# Mono_Audio_Amp_TPA2005D1_v10.net
KiCad netlist of a schematic drawn in EAGLE
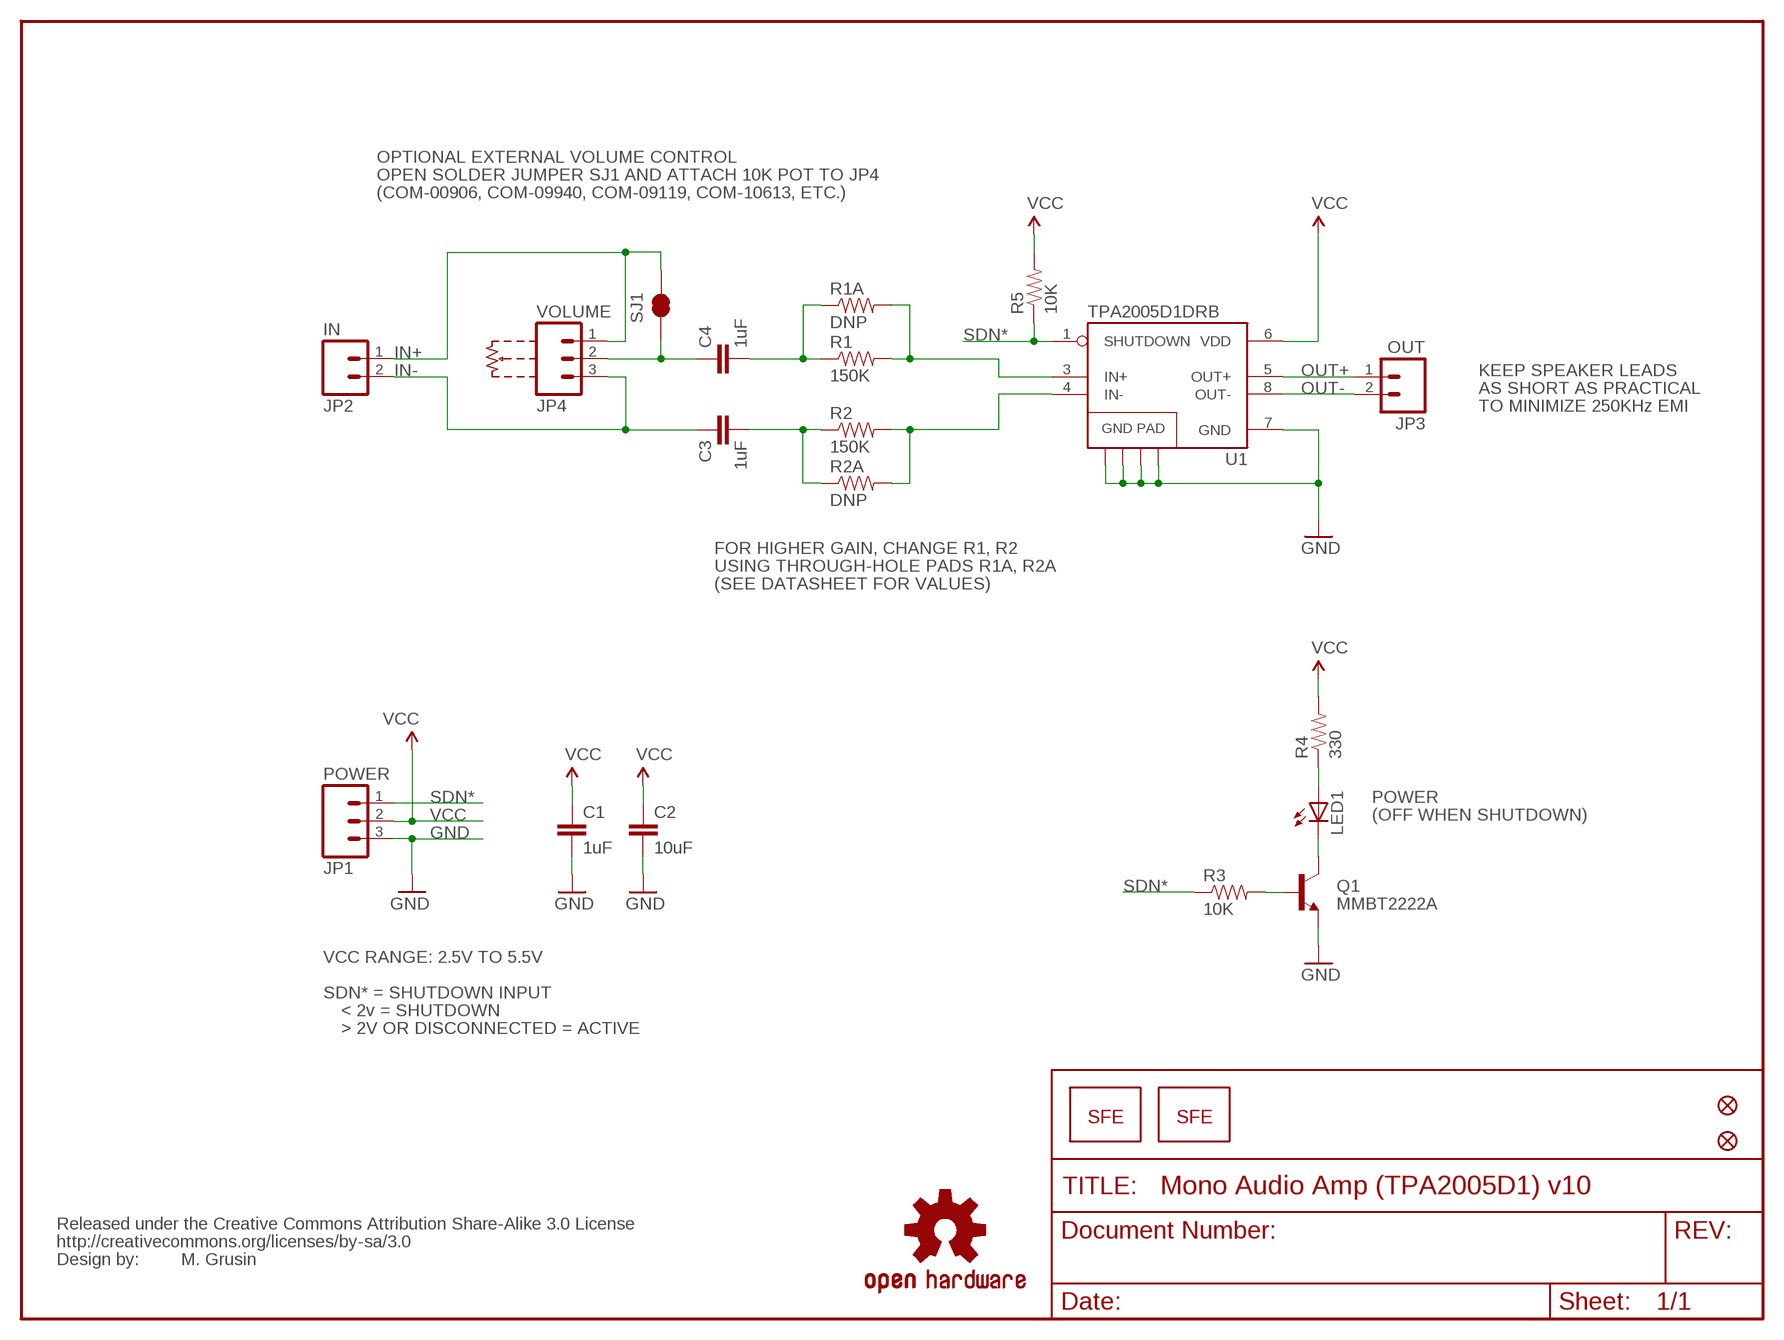
[diagram p0: schematic, sheet 1]

(export (version "E")
  (design (tool "Eeschema 10.0.6"))
  (components
    (comp (ref "C1")
      (value "1uF")
      (footprint "eagle-import:1206")
      (libsource (lib "eagle-import") (part "CAP1206"))
    )
    (comp (ref "C2")
      (value "10uF")
      (footprint "eagle-import:1206")
      (libsource (lib "eagle-import") (part "CAP1206"))
    )
    (comp (ref "C3")
      (value "1uF")
      (footprint "eagle-import:1206")
      (libsource (lib "eagle-import") (part "CAP1206"))
    )
    (comp (ref "C4")
      (value "1uF")
      (footprint "eagle-import:1206")
      (libsource (lib "eagle-import") (part "CAP1206"))
    )
    (comp (ref "JP1")
      (value "POWER")
      (footprint "eagle-import:1X03")
      (libsource (lib "eagle-import") (part "M03PTH"))
    )
    (comp (ref "JP2")
      (value "IN")
      (footprint "eagle-import:1X02")
      (libsource (lib "eagle-import") (part "M02PTH"))
    )
    (comp (ref "JP3")
      (value "OUT")
      (footprint "eagle-import:1X02")
      (libsource (lib "eagle-import") (part "M02PTH"))
    )
    (comp (ref "JP4")
      (value "VOLUME")
      (footprint "eagle-import:1X03")
      (libsource (lib "eagle-import") (part "M03PTH"))
    )
    (comp (ref "JP5")
      (value "FIDUCIALUFIDUCIAL")
      (footprint "eagle-import:MICRO-FIDUCIAL")
      (libsource (lib "eagle-import") (part "FIDUCIALUFIDUCIAL"))
    )
    (comp (ref "JP6")
      (value "FIDUCIALUFIDUCIAL")
      (footprint "eagle-import:MICRO-FIDUCIAL")
      (libsource (lib "eagle-import") (part "FIDUCIALUFIDUCIAL"))
    )
    (comp (ref "LED1")
      (value "LED0603")
      (footprint "eagle-import:LED-0603")
      (libsource (lib "eagle-import") (part "LED0603"))
    )
    (comp (ref "LOGO1")
      (value "LOGO-SFENW2")
      (footprint "eagle-import:SFE-NEW-WEB")
      (libsource (lib "eagle-import") (part "LOGO-SFENW2"))
    )
    (comp (ref "LOGO2")
      (value "LOGO-SFESK")
      (footprint "eagle-import:SFE-LOGO-FLAME")
      (libsource (lib "eagle-import") (part "LOGO-SFESK"))
    )
    (comp (ref "Q1")
      (value "MMBT2222A")
      (footprint "eagle-import:SOT23-3")
      (libsource (lib "eagle-import") (part "TRANSISTOR_NPNSOT23-3"))
    )
    (comp (ref "R1")
      (value "150K")
      (footprint "eagle-import:0603-RES")
      (libsource (lib "eagle-import") (part "RESISTOR0603-RES"))
    )
    (comp (ref "R1A")
      (value "DNP")
      (footprint "eagle-import:AXIAL-0.3")
      (libsource (lib "eagle-import") (part "RESISTORAXIAL-0.3"))
    )
    (comp (ref "R2")
      (value "150K")
      (footprint "eagle-import:0603-RES")
      (libsource (lib "eagle-import") (part "RESISTOR0603-RES"))
    )
    (comp (ref "R2A")
      (value "DNP")
      (footprint "eagle-import:AXIAL-0.3")
      (libsource (lib "eagle-import") (part "RESISTORAXIAL-0.3"))
    )
    (comp (ref "R3")
      (value "10K")
      (footprint "eagle-import:0603-RES")
      (libsource (lib "eagle-import") (part "RESISTOR0603-RES"))
    )
    (comp (ref "R4")
      (value "330")
      (footprint "eagle-import:0603-RES")
      (libsource (lib "eagle-import") (part "RESISTOR0603-RES"))
    )
    (comp (ref "R5")
      (value "10K")
      (footprint "eagle-import:0603-RES")
      (libsource (lib "eagle-import") (part "RESISTOR0603-RES"))
    )
    (comp (ref "SJ1")
      (value "SOLDERJUMPERNC2")
      (footprint "eagle-import:SJ_2S-NOTRACE")
      (libsource (lib "eagle-import") (part "SOLDERJUMPERNC2"))
    )
    (comp (ref "U$1")
      (value "CREATIVE_COMMONS")
      (footprint "eagle-import:CREATIVE_COMMONS")
      (libsource (lib "eagle-import") (part "CREATIVE_COMMONS"))
    )
    (comp (ref "U$2")
      (value "OSHW-LOGOS")
      (footprint "eagle-import:OSHW-LOGO-S")
      (libsource (lib "eagle-import") (part "OSHW-LOGOS"))
    )
    (comp (ref "U1")
      (value "TPA2005D1DRB")
      (footprint "eagle-import:QFN-8_PAD")
      (libsource (lib "eagle-import") (part "TPA2005D1DRB"))
    )
  )
  (nets
    (net (code "1") (name "/IN+") (class "Default")
      (node (ref "JP2") (pin "1") (pinfunction "1_1") (pintype "passive"))
      (node (ref "JP4") (pin "1") (pinfunction "1_1") (pintype "passive"))
      (node (ref "SJ1") (pin "2") (pinfunction "2_2") (pintype "passive"))
    )
    (net (code "2") (name "/IN-") (class "Default")
      (node (ref "C3") (pin "1") (pinfunction "1_1") (pintype "passive"))
      (node (ref "JP2") (pin "2") (pinfunction "2_2") (pintype "passive"))
      (node (ref "JP4") (pin "3") (pinfunction "3_3") (pintype "passive"))
    )
    (net (code "3") (name "/OUT+") (class "Default")
      (node (ref "JP3") (pin "1") (pinfunction "1_1") (pintype "passive"))
      (node (ref "U1") (pin "5") (pinfunction "OUT+_5") (pintype "bidirectional"))
    )
    (net (code "4") (name "/OUT-") (class "Default")
      (node (ref "JP3") (pin "2") (pinfunction "2_2") (pintype "passive"))
      (node (ref "U1") (pin "8") (pinfunction "OUT-_8") (pintype "bidirectional"))
    )
    (net (code "5") (name "/SDN*") (class "Default")
      (node (ref "JP1") (pin "1") (pinfunction "1_1") (pintype "passive"))
      (node (ref "R3") (pin "1") (pinfunction "1_1") (pintype "passive"))
      (node (ref "R5") (pin "1") (pinfunction "1_1") (pintype "passive"))
      (node (ref "U1") (pin "1") (pinfunction "SHUTDOWN_1") (pintype "input"))
    )
    (net (code "6") (name "GND") (class "Default")
      (node (ref "C1") (pin "2") (pinfunction "2_2") (pintype "passive"))
      (node (ref "C2") (pin "2") (pinfunction "2_2") (pintype "passive"))
      (node (ref "JP1") (pin "3") (pinfunction "3_3") (pintype "passive"))
      (node (ref "Q1") (pin "2") (pinfunction "E_2") (pintype "passive"))
      (node (ref "U1") (pin "10") (pinfunction "GND_10") (pintype "power_in"))
      (node (ref "U1") (pin "11") (pinfunction "GND_11") (pintype "power_in"))
      (node (ref "U1") (pin "12") (pinfunction "GND_12") (pintype "bidirectional"))
      (node (ref "U1") (pin "13") (pinfunction "GND_13") (pintype "bidirectional"))
      (node (ref "U1") (pin "7") (pinfunction "GND_7") (pintype "power_in"))
    )
    (net (code "7") (name "Net-(C4-Pad1)") (class "Default")
      (node (ref "C4") (pin "1") (pinfunction "1_1") (pintype "passive"))
      (node (ref "JP4") (pin "2") (pinfunction "2_2") (pintype "passive"))
      (node (ref "SJ1") (pin "1") (pinfunction "1_1") (pintype "passive"))
    )
    (net (code "8") (name "Net-(LED1-PadA)") (class "Default")
      (node (ref "LED1") (pin "A") (pinfunction "A_A") (pintype "passive"))
      (node (ref "R4") (pin "1") (pinfunction "1_1") (pintype "passive"))
    )
    (net (code "9") (name "Net-(Q1-B)") (class "Default")
      (node (ref "Q1") (pin "1") (pinfunction "B_1") (pintype "passive"))
      (node (ref "R3") (pin "2") (pinfunction "2_2") (pintype "passive"))
    )
    (net (code "10") (name "Net-(Q1-C)") (class "Default")
      (node (ref "LED1") (pin "C") (pinfunction "C_C") (pintype "passive"))
      (node (ref "Q1") (pin "3") (pinfunction "C_3") (pintype "passive"))
    )
    (net (code "11") (name "Net-(R1A-1)") (class "Default")
      (node (ref "C4") (pin "2") (pinfunction "2_2") (pintype "passive"))
      (node (ref "R1") (pin "1") (pinfunction "1_1") (pintype "passive"))
      (node (ref "R1A") (pin "P$1") (pinfunction "1_P$1") (pintype "passive"))
    )
    (net (code "12") (name "Net-(R1A-2)") (class "Default")
      (node (ref "R1") (pin "2") (pinfunction "2_2") (pintype "passive"))
      (node (ref "R1A") (pin "P$2") (pinfunction "2_P$2") (pintype "passive"))
      (node (ref "U1") (pin "3") (pinfunction "IN+_3") (pintype "bidirectional"))
    )
    (net (code "13") (name "Net-(R2A-1)") (class "Default")
      (node (ref "C3") (pin "2") (pinfunction "2_2") (pintype "passive"))
      (node (ref "R2") (pin "1") (pinfunction "1_1") (pintype "passive"))
      (node (ref "R2A") (pin "P$1") (pinfunction "1_P$1") (pintype "passive"))
    )
    (net (code "14") (name "Net-(R2A-2)") (class "Default")
      (node (ref "R2") (pin "2") (pinfunction "2_2") (pintype "passive"))
      (node (ref "R2A") (pin "P$2") (pinfunction "2_P$2") (pintype "passive"))
      (node (ref "U1") (pin "4") (pinfunction "IN-_4") (pintype "bidirectional"))
    )
    (net (code "15") (name "VCC") (class "Default")
      (node (ref "C1") (pin "1") (pinfunction "1_1") (pintype "passive"))
      (node (ref "C2") (pin "1") (pinfunction "1_1") (pintype "passive"))
      (node (ref "JP1") (pin "2") (pinfunction "2_2") (pintype "passive"))
      (node (ref "R4") (pin "2") (pinfunction "2_2") (pintype "passive"))
      (node (ref "R5") (pin "2") (pinfunction "2_2") (pintype "passive"))
      (node (ref "U1") (pin "6") (pinfunction "VDD_6") (pintype "power_in"))
    )
  )
)
